# CurrentStabilizer_VER2.net
KiCad netlist of a schematic drawn in EAGLE
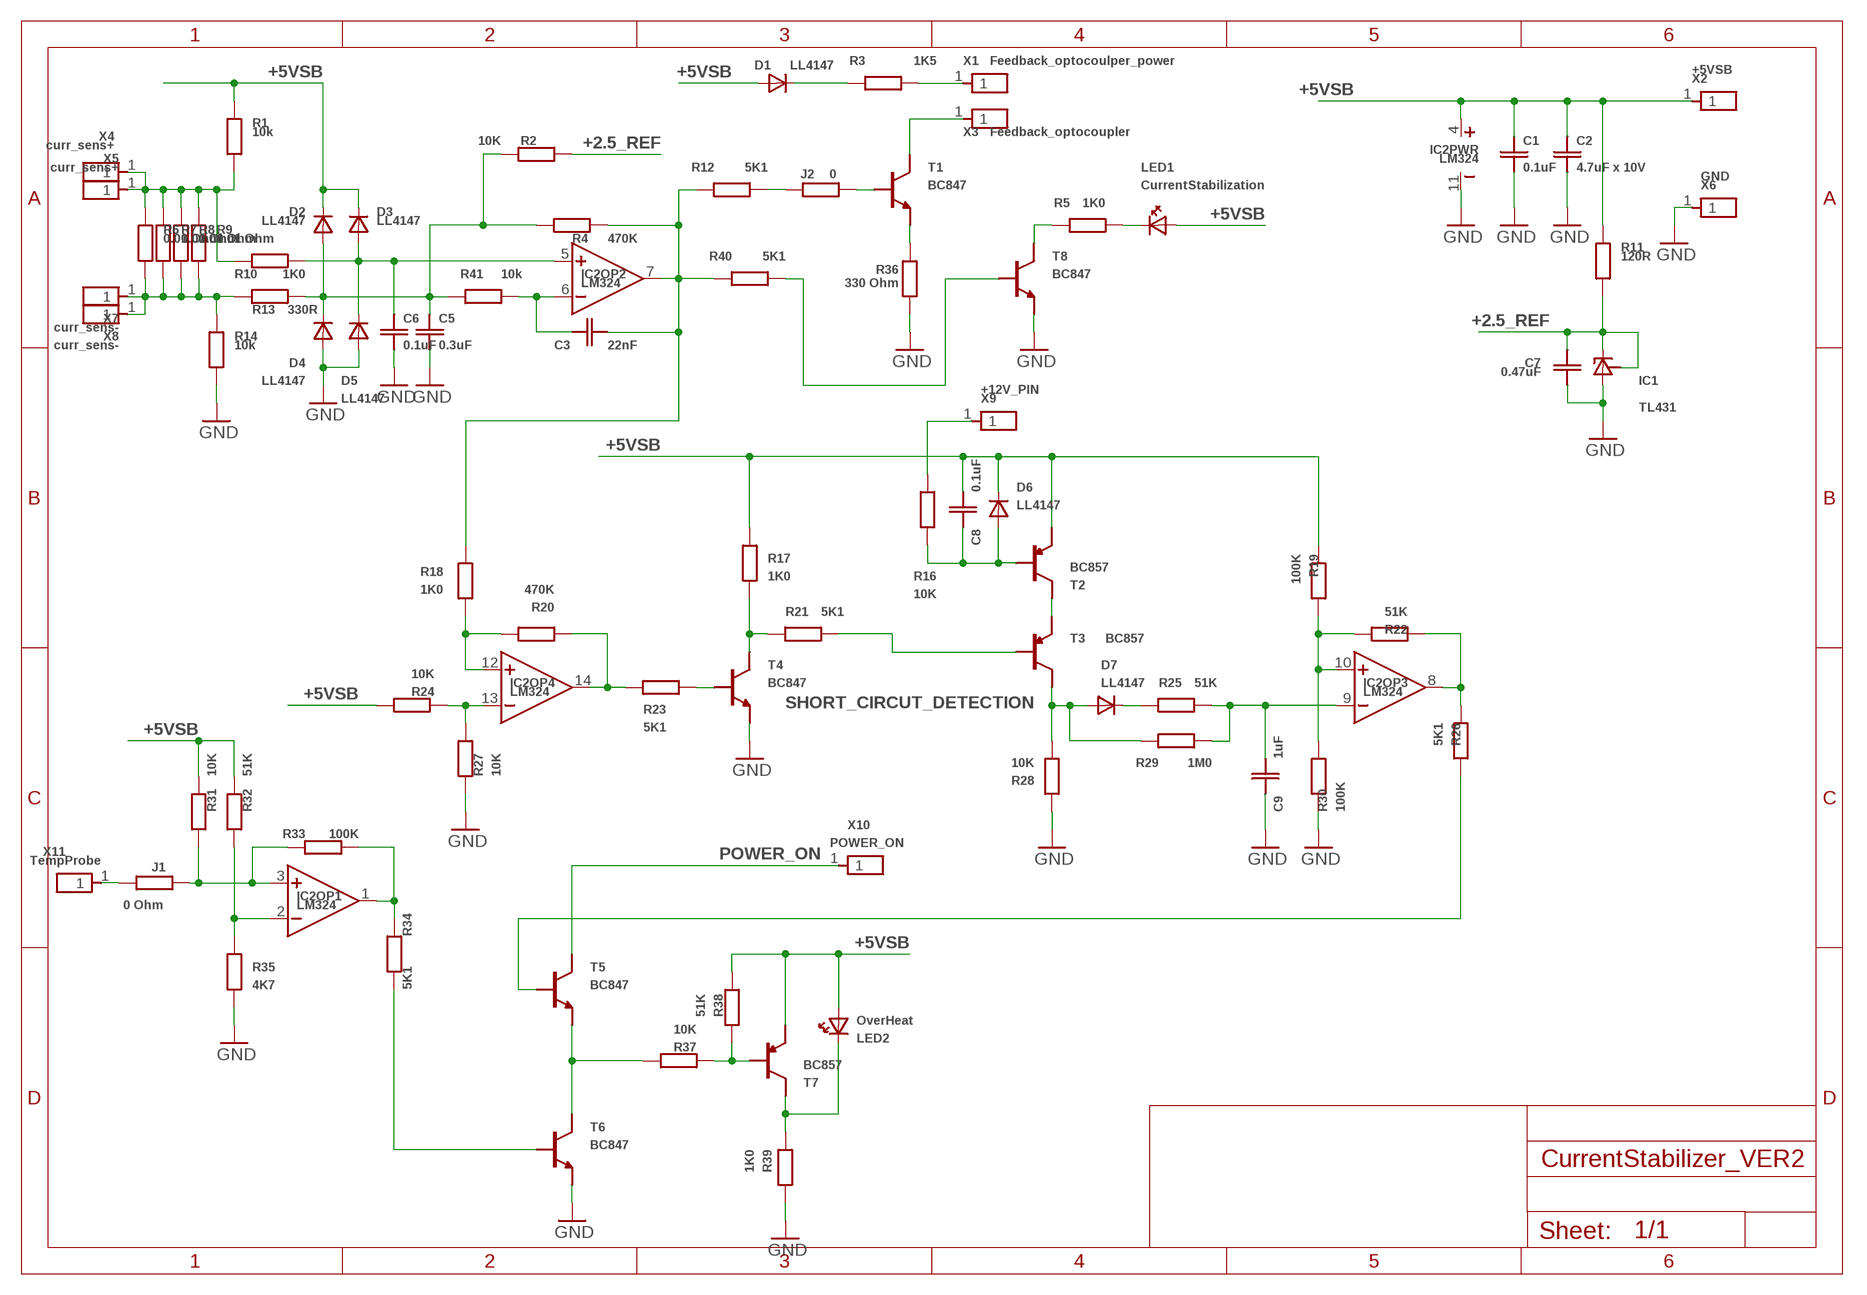
[diagram p0: schematic, sheet 1]

(export (version "E")
  (design (tool "Eeschema 10.0.6"))
  (components
    (comp (ref "C1")
      (value "0.1uF")
      (footprint "eagle-import:RSMD_0805")
      (libsource (lib "eagle-import") (part "CSMD_0805"))
    )
    (comp (ref "C2")
      (value "4.7uF x 10V")
      (footprint "eagle-import:RSMD_1206")
      (libsource (lib "eagle-import") (part "CSMD_1206"))
    )
    (comp (ref "C3")
      (value "22nF")
      (footprint "eagle-import:RSMD_0805")
      (libsource (lib "eagle-import") (part "CSMD_0805"))
    )
    (comp (ref "C5")
      (value "0.3uF")
      (footprint "eagle-import:RSMD_0805")
      (libsource (lib "eagle-import") (part "CSMD_0805"))
    )
    (comp (ref "C6")
      (value "0.1uF")
      (footprint "eagle-import:RSMD_0805")
      (libsource (lib "eagle-import") (part "CSMD_0805"))
    )
    (comp (ref "C7")
      (value "0.47uF")
      (footprint "eagle-import:RSMD_0805")
      (libsource (lib "eagle-import") (part "CSMD_0805"))
    )
    (comp (ref "C8")
      (value "0.1uF")
      (footprint "eagle-import:RSMD_0805")
      (libsource (lib "eagle-import") (part "CSMD_0805"))
    )
    (comp (ref "C9")
      (value "1uF")
      (footprint "eagle-import:RSMD_0805")
      (libsource (lib "eagle-import") (part "CSMD_0805"))
    )
    (comp (ref "D1")
      (value "LL4147")
      (footprint "eagle-import:SOD-80")
      (libsource (lib "eagle-import") (part "LL4147SOD-80"))
    )
    (comp (ref "D2")
      (value "LL4147")
      (footprint "eagle-import:SOD-80")
      (libsource (lib "eagle-import") (part "LL4147SOD-80"))
    )
    (comp (ref "D3")
      (value "LL4147")
      (footprint "eagle-import:SOD-80")
      (libsource (lib "eagle-import") (part "LL4147SOD-80"))
    )
    (comp (ref "D4")
      (value "LL4147")
      (footprint "eagle-import:SOD-80")
      (libsource (lib "eagle-import") (part "LL4147SOD-80"))
    )
    (comp (ref "D5")
      (value "LL4147")
      (footprint "eagle-import:SOD-80")
      (libsource (lib "eagle-import") (part "LL4147SOD-80"))
    )
    (comp (ref "D6")
      (value "LL4147")
      (footprint "eagle-import:SOD-80")
      (libsource (lib "eagle-import") (part "LL4147SOD-80"))
    )
    (comp (ref "D7")
      (value "LL4147")
      (footprint "eagle-import:SOD-80")
      (libsource (lib "eagle-import") (part "LL4147SOD-80"))
    )
    (comp (ref "IC1")
      (value "TL431")
      (footprint "eagle-import:SOT23")
      (libsource (lib "eagle-import") (part "TL431SOT23"))
    )
    (comp (ref "IC2")
      (value "LM324")
      (footprint "eagle-import:SOIC14")
      (libsource (lib "eagle-import") (part "LM324"))
    )
    (comp (ref "J1")
      (value "0 Ohm")
      (footprint "eagle-import:RSMD_0805")
      (libsource (lib "eagle-import") (part "RSMD_0805"))
    )
    (comp (ref "J2")
      (value "0")
      (footprint "eagle-import:RSMD_0805")
      (libsource (lib "eagle-import") (part "RSMD_0805"))
    )
    (comp (ref "LED1")
      (value "CurrentStabilization")
      (footprint "eagle-import:LED3MM")
      (libsource (lib "eagle-import") (part "LED3MM"))
    )
    (comp (ref "LED2")
      (value "OverHeat")
      (footprint "eagle-import:LED3MM")
      (libsource (lib "eagle-import") (part "LED3MM"))
    )
    (comp (ref "R1")
      (value "10k")
      (footprint "eagle-import:RSMD_0805")
      (libsource (lib "eagle-import") (part "RSMD_0805"))
    )
    (comp (ref "R2")
      (value "10K")
      (footprint "eagle-import:RSMD_0805")
      (libsource (lib "eagle-import") (part "RSMD_0805"))
    )
    (comp (ref "R3")
      (value "1K5")
      (footprint "eagle-import:RSMD_0805")
      (libsource (lib "eagle-import") (part "RSMD_0805"))
    )
    (comp (ref "R4")
      (value "470K")
      (footprint "eagle-import:RSMD_0805")
      (libsource (lib "eagle-import") (part "RSMD_0805"))
    )
    (comp (ref "R5")
      (value "1K0")
      (footprint "eagle-import:RSMD_0805")
      (libsource (lib "eagle-import") (part "RSMD_0805"))
    )
    (comp (ref "R6")
      (value "0.01 Ohm")
      (footprint "eagle-import:RSMD_2512")
      (libsource (lib "eagle-import") (part "RSMD_2512"))
    )
    (comp (ref "R7")
      (value "0.01 Ohm")
      (footprint "eagle-import:RSMD_2512")
      (libsource (lib "eagle-import") (part "RSMD_2512"))
    )
    (comp (ref "R8")
      (value "0.01 Ohm")
      (footprint "eagle-import:RSMD_2512")
      (libsource (lib "eagle-import") (part "RSMD_2512"))
    )
    (comp (ref "R9")
      (value "0.01 Ohm")
      (footprint "eagle-import:RSMD_2512")
      (libsource (lib "eagle-import") (part "RSMD_2512"))
    )
    (comp (ref "R10")
      (value "1K0")
      (footprint "eagle-import:RSMD_0805")
      (libsource (lib "eagle-import") (part "RSMD_0805"))
    )
    (comp (ref "R11")
      (value "120R")
      (footprint "eagle-import:RSMD_0805")
      (libsource (lib "eagle-import") (part "RSMD_0805"))
    )
    (comp (ref "R12")
      (value "5K1")
      (footprint "eagle-import:RSMD_0805")
      (libsource (lib "eagle-import") (part "RSMD_0805"))
    )
    (comp (ref "R13")
      (value "330R")
      (footprint "eagle-import:RSMD_0805")
      (libsource (lib "eagle-import") (part "RSMD_0805"))
    )
    (comp (ref "R14")
      (value "10k")
      (footprint "eagle-import:RSMD_0805")
      (libsource (lib "eagle-import") (part "RSMD_0805"))
    )
    (comp (ref "R16")
      (value "10K")
      (footprint "eagle-import:RSMD_0805")
      (libsource (lib "eagle-import") (part "RSMD_0805"))
    )
    (comp (ref "R17")
      (value "1K0")
      (footprint "eagle-import:RSMD_0805")
      (libsource (lib "eagle-import") (part "RSMD_0805"))
    )
    (comp (ref "R18")
      (value "1K0")
      (footprint "eagle-import:RSMD_0805")
      (libsource (lib "eagle-import") (part "RSMD_0805"))
    )
    (comp (ref "R19")
      (value "100K")
      (footprint "eagle-import:RSMD_1206_BIG_GAP")
      (libsource (lib "eagle-import") (part "RSMD_1206_BIG_GAP"))
    )
    (comp (ref "R20")
      (value "470K")
      (footprint "eagle-import:RSMD_0805")
      (libsource (lib "eagle-import") (part "RSMD_0805"))
    )
    (comp (ref "R21")
      (value "5K1")
      (footprint "eagle-import:RSMD_0805")
      (libsource (lib "eagle-import") (part "RSMD_0805"))
    )
    (comp (ref "R22")
      (value "51K")
      (footprint "eagle-import:RSMD_0805")
      (libsource (lib "eagle-import") (part "RSMD_0805"))
    )
    (comp (ref "R23")
      (value "5K1")
      (footprint "eagle-import:RSMD_1206_BIG_GAP")
      (libsource (lib "eagle-import") (part "RSMD_1206_BIG_GAP"))
    )
    (comp (ref "R24")
      (value "10K")
      (footprint "eagle-import:RSMD_0805")
      (libsource (lib "eagle-import") (part "RSMD_0805"))
    )
    (comp (ref "R25")
      (value "51K")
      (footprint "eagle-import:RSMD_0805")
      (libsource (lib "eagle-import") (part "RSMD_0805"))
    )
    (comp (ref "R26")
      (value "5K1")
      (footprint "eagle-import:RSMD_0805")
      (libsource (lib "eagle-import") (part "RSMD_0805"))
    )
    (comp (ref "R27")
      (value "10K")
      (footprint "eagle-import:RSMD_0805")
      (libsource (lib "eagle-import") (part "RSMD_0805"))
    )
    (comp (ref "R28")
      (value "10K")
      (footprint "eagle-import:RSMD_0805")
      (libsource (lib "eagle-import") (part "RSMD_0805"))
    )
    (comp (ref "R29")
      (value "1M0")
      (footprint "eagle-import:RSMD_0805")
      (libsource (lib "eagle-import") (part "RSMD_0805"))
    )
    (comp (ref "R30")
      (value "100K")
      (footprint "eagle-import:RSMD_0805")
      (libsource (lib "eagle-import") (part "RSMD_0805"))
    )
    (comp (ref "R31")
      (value "10K")
      (footprint "eagle-import:RSMD_0805")
      (libsource (lib "eagle-import") (part "RSMD_0805"))
    )
    (comp (ref "R32")
      (value "51K")
      (footprint "eagle-import:RSMD_0805")
      (libsource (lib "eagle-import") (part "RSMD_0805"))
    )
    (comp (ref "R33")
      (value "100K")
      (footprint "eagle-import:RSMD_0805")
      (libsource (lib "eagle-import") (part "RSMD_0805"))
    )
    (comp (ref "R34")
      (value "5K1")
      (footprint "eagle-import:RSMD_0805")
      (libsource (lib "eagle-import") (part "RSMD_0805"))
    )
    (comp (ref "R35")
      (value "4K7")
      (footprint "eagle-import:RSMD_0805")
      (libsource (lib "eagle-import") (part "RSMD_0805"))
    )
    (comp (ref "R36")
      (value "330 Ohm")
      (footprint "eagle-import:RSMD_0805")
      (libsource (lib "eagle-import") (part "RSMD_0805"))
    )
    (comp (ref "R37")
      (value "10K")
      (footprint "eagle-import:RSMD_1206_BIG_GAP")
      (libsource (lib "eagle-import") (part "RSMD_1206_BIG_GAP"))
    )
    (comp (ref "R38")
      (value "51K")
      (footprint "eagle-import:RSMD_0805")
      (libsource (lib "eagle-import") (part "RSMD_0805"))
    )
    (comp (ref "R39")
      (value "1K0")
      (footprint "eagle-import:RSMD_0805")
      (libsource (lib "eagle-import") (part "RSMD_0805"))
    )
    (comp (ref "R40")
      (value "5K1")
      (footprint "eagle-import:RSMD_0805")
      (libsource (lib "eagle-import") (part "RSMD_0805"))
    )
    (comp (ref "R41")
      (value "10k")
      (footprint "eagle-import:RSMD_0805")
      (libsource (lib "eagle-import") (part "RSMD_0805"))
    )
    (comp (ref "T1")
      (value "BC847")
      (footprint "eagle-import:SOT23_SMALL_PADS")
      (libsource (lib "eagle-import") (part "BC847SOT23_SMALL_PADS"))
    )
    (comp (ref "T2")
      (value "BC857")
      (footprint "eagle-import:SOT23_SMALL_PADS")
      (libsource (lib "eagle-import") (part "BC857SOT23_SMALL_PADS"))
    )
    (comp (ref "T3")
      (value "BC857")
      (footprint "eagle-import:SOT23_SMALL_PADS")
      (libsource (lib "eagle-import") (part "BC857SOT23_SMALL_PADS"))
    )
    (comp (ref "T4")
      (value "BC847")
      (footprint "eagle-import:SOT23_SMALL_PADS")
      (libsource (lib "eagle-import") (part "BC847SOT23_SMALL_PADS"))
    )
    (comp (ref "T5")
      (value "BC847")
      (footprint "eagle-import:SOT23_SMALL_PADS")
      (libsource (lib "eagle-import") (part "BC847SOT23_SMALL_PADS"))
    )
    (comp (ref "T6")
      (value "BC847")
      (footprint "eagle-import:SOT23_SMALL_PADS")
      (libsource (lib "eagle-import") (part "BC847SOT23_SMALL_PADS"))
    )
    (comp (ref "T7")
      (value "BC857")
      (footprint "eagle-import:SOT23_SMALL_PADS")
      (libsource (lib "eagle-import") (part "BC857SOT23_SMALL_PADS"))
    )
    (comp (ref "T8")
      (value "BC847")
      (footprint "eagle-import:SOT23_SMALL_PADS")
      (libsource (lib "eagle-import") (part "BC847SOT23_SMALL_PADS"))
    )
    (comp (ref "X1")
      (value "Feedback_optocoulper_power")
      (footprint "eagle-import:PIN1X1_2.54MM")
      (libsource (lib "eagle-import") (part "PIN1X12.54MM"))
    )
    (comp (ref "X2")
      (value "+5VSB")
      (footprint "eagle-import:PIN1X1_2.54MM")
      (libsource (lib "eagle-import") (part "PIN1X12.54MM"))
    )
    (comp (ref "X3")
      (value "Feedback_optocoupler")
      (footprint "eagle-import:PIN1X1_2.54MM")
      (libsource (lib "eagle-import") (part "PIN1X12.54MM"))
    )
    (comp (ref "X4")
      (value "curr_sens+")
      (footprint "eagle-import:PIN1X1_2.54MM")
      (libsource (lib "eagle-import") (part "PIN1X12.54MM"))
    )
    (comp (ref "X5")
      (value "curr_sens+")
      (footprint "eagle-import:PIN1X1_2.54MM")
      (libsource (lib "eagle-import") (part "PIN1X12.54MM"))
    )
    (comp (ref "X6")
      (value "GND")
      (footprint "eagle-import:PIN1X1_2.54MM")
      (libsource (lib "eagle-import") (part "PIN1X12.54MM"))
    )
    (comp (ref "X7")
      (value "curr_sens-")
      (footprint "eagle-import:PIN1X1_2.54MM")
      (libsource (lib "eagle-import") (part "PIN1X12.54MM"))
    )
    (comp (ref "X8")
      (value "curr_sens-")
      (footprint "eagle-import:PIN1X1_2.54MM")
      (libsource (lib "eagle-import") (part "PIN1X12.54MM"))
    )
    (comp (ref "X9")
      (value "+12V_PIN")
      (footprint "eagle-import:PIN1X1_2.54MM")
      (libsource (lib "eagle-import") (part "PIN1X12.54MM"))
    )
    (comp (ref "X10")
      (value "POWER_ON")
      (footprint "eagle-import:PIN1X1_2.54MM")
      (libsource (lib "eagle-import") (part "PIN1X12.54MM"))
    )
    (comp (ref "X11")
      (value "TempProbe")
      (footprint "eagle-import:PIN1X1_2.54MM")
      (libsource (lib "eagle-import") (part "PIN1X12.54MM"))
    )
  )
  (nets
    (net (code "1") (name "/+2.5_REF") (class "Default")
      (node (ref "C7") (pin "PAD_1") (pinfunction "PIN1_PAD_1") (pintype "bidirectional"))
      (node (ref "IC1") (pin "1") (pinfunction "CATHODE_1") (pintype "passive"))
      (node (ref "IC1") (pin "2") (pinfunction "REFERENCE_2") (pintype "passive"))
      (node (ref "R11") (pin "PAD_0") (pinfunction "PIN0_PAD_0") (pintype "passive"))
      (node (ref "R2") (pin "PAD_0") (pinfunction "PIN0_PAD_0") (pintype "passive"))
    )
    (net (code "2") (name "/+5VSB") (class "Default")
      (node (ref "C1") (pin "PAD_1") (pinfunction "PIN1_PAD_1") (pintype "bidirectional"))
      (node (ref "C2") (pin "PAD_1") (pinfunction "PIN1_PAD_1") (pintype "bidirectional"))
      (node (ref "C8") (pin "PAD_0") (pinfunction "PIN0_PAD_0") (pintype "bidirectional"))
      (node (ref "D1") (pin "ANODE") (pinfunction "ANODE_ANODE") (pintype "passive"))
      (node (ref "D2") (pin "CATHODE") (pinfunction "CATHODE_CATHODE") (pintype "passive"))
      (node (ref "D3") (pin "CATHODE") (pinfunction "CATHODE_CATHODE") (pintype "passive"))
      (node (ref "D6") (pin "CATHODE") (pinfunction "CATHODE_CATHODE") (pintype "passive"))
      (node (ref "IC2") (pin "4") (pinfunction "VCC_4") (pintype "power_in"))
      (node (ref "LED1") (pin "ANODE") (pinfunction "ANODE_ANODE") (pintype "passive"))
      (node (ref "LED2") (pin "ANODE") (pinfunction "ANODE_ANODE") (pintype "passive"))
      (node (ref "R1") (pin "PAD_1") (pinfunction "PIN1_PAD_1") (pintype "passive"))
      (node (ref "R11") (pin "PAD_1") (pinfunction "PIN1_PAD_1") (pintype "passive"))
      (node (ref "R17") (pin "PAD_0") (pinfunction "PIN0_PAD_0") (pintype "passive"))
      (node (ref "R19") (pin "PAD_0") (pinfunction "PIN0_PAD_0") (pintype "passive"))
      (node (ref "R24") (pin "PAD_1") (pinfunction "PIN1_PAD_1") (pintype "passive"))
      (node (ref "R31") (pin "PAD_1") (pinfunction "PIN1_PAD_1") (pintype "passive"))
      (node (ref "R32") (pin "PAD_1") (pinfunction "PIN1_PAD_1") (pintype "passive"))
      (node (ref "R38") (pin "PAD_0") (pinfunction "PIN0_PAD_0") (pintype "passive"))
      (node (ref "T2") (pin "2") (pinfunction "E_2") (pintype "bidirectional"))
      (node (ref "T7") (pin "2") (pinfunction "E_2") (pintype "bidirectional"))
      (node (ref "X2") (pin "1") (pinfunction "1_1") (pintype "bidirectional"))
    )
    (net (code "3") (name "/POWER_ON") (class "Default")
      (node (ref "T5") (pin "3") (pinfunction "C_3") (pintype "bidirectional"))
      (node (ref "X10") (pin "1") (pinfunction "1_1") (pintype "bidirectional"))
    )
    (net (code "4") (name "/SHORT_CIRCUT_DETECTION") (class "Default")
      (node (ref "D7") (pin "ANODE") (pinfunction "ANODE_ANODE") (pintype "passive"))
      (node (ref "R28") (pin "PAD_0") (pinfunction "PIN0_PAD_0") (pintype "passive"))
      (node (ref "R29") (pin "PAD_1") (pinfunction "PIN1_PAD_1") (pintype "passive"))
      (node (ref "T3") (pin "3") (pinfunction "C_3") (pintype "bidirectional"))
    )
    (net (code "5") (name "GND") (class "Default")
      (node (ref "C1") (pin "PAD_0") (pinfunction "PIN0_PAD_0") (pintype "bidirectional"))
      (node (ref "C2") (pin "PAD_0") (pinfunction "PIN0_PAD_0") (pintype "bidirectional"))
      (node (ref "C5") (pin "PAD_0") (pinfunction "PIN0_PAD_0") (pintype "bidirectional"))
      (node (ref "C6") (pin "PAD_0") (pinfunction "PIN0_PAD_0") (pintype "bidirectional"))
      (node (ref "C7") (pin "PAD_0") (pinfunction "PIN0_PAD_0") (pintype "bidirectional"))
      (node (ref "C9") (pin "PAD_1") (pinfunction "PIN1_PAD_1") (pintype "bidirectional"))
      (node (ref "D4") (pin "ANODE") (pinfunction "ANODE_ANODE") (pintype "passive"))
      (node (ref "D5") (pin "ANODE") (pinfunction "ANODE_ANODE") (pintype "passive"))
      (node (ref "IC1") (pin "3") (pinfunction "ANODE_3") (pintype "passive"))
      (node (ref "IC2") (pin "11") (pinfunction "GND_11") (pintype "power_in"))
      (node (ref "R14") (pin "PAD_0") (pinfunction "PIN0_PAD_0") (pintype "passive"))
      (node (ref "R27") (pin "PAD_0") (pinfunction "PIN0_PAD_0") (pintype "passive"))
      (node (ref "R28") (pin "PAD_1") (pinfunction "PIN1_PAD_1") (pintype "passive"))
      (node (ref "R30") (pin "PAD_0") (pinfunction "PIN0_PAD_0") (pintype "passive"))
      (node (ref "R35") (pin "PAD_0") (pinfunction "PIN0_PAD_0") (pintype "passive"))
      (node (ref "R36") (pin "PAD_0") (pinfunction "PIN0_PAD_0") (pintype "passive"))
      (node (ref "R39") (pin "PAD_1") (pinfunction "PIN1_PAD_1") (pintype "passive"))
      (node (ref "T4") (pin "2") (pinfunction "E_2") (pintype "bidirectional"))
      (node (ref "T6") (pin "2") (pinfunction "E_2") (pintype "bidirectional"))
      (node (ref "T8") (pin "2") (pinfunction "E_2") (pintype "bidirectional"))
      (node (ref "X6") (pin "1") (pinfunction "1_1") (pintype "bidirectional"))
    )
    (net (code "6") (name "Net-(C3-PIN0)") (class "Default")
      (node (ref "C3") (pin "PAD_0") (pinfunction "PIN0_PAD_0") (pintype "bidirectional"))
      (node (ref "IC2") (pin "7") (pinfunction "OUT_7") (pintype "output"))
      (node (ref "R12") (pin "PAD_1") (pinfunction "PIN1_PAD_1") (pintype "passive"))
      (node (ref "R18") (pin "PAD_1") (pinfunction "PIN1_PAD_1") (pintype "passive"))
      (node (ref "R4") (pin "PAD_1") (pinfunction "PIN1_PAD_1") (pintype "passive"))
      (node (ref "R40") (pin "PAD_1") (pinfunction "PIN1_PAD_1") (pintype "passive"))
    )
    (net (code "7") (name "Net-(C3-PIN1)") (class "Default")
      (node (ref "C3") (pin "PAD_1") (pinfunction "PIN1_PAD_1") (pintype "bidirectional"))
      (node (ref "IC2") (pin "6") (pinfunction "IN-_6") (pintype "input"))
      (node (ref "R41") (pin "PAD_0") (pinfunction "PIN0_PAD_0") (pintype "passive"))
    )
    (net (code "8") (name "Net-(C5-PIN1)") (class "Default")
      (node (ref "C5") (pin "PAD_1") (pinfunction "PIN1_PAD_1") (pintype "bidirectional"))
      (node (ref "D2") (pin "ANODE") (pinfunction "ANODE_ANODE") (pintype "passive"))
      (node (ref "D4") (pin "CATHODE") (pinfunction "CATHODE_CATHODE") (pintype "passive"))
      (node (ref "R13") (pin "PAD_1") (pinfunction "PIN1_PAD_1") (pintype "passive"))
      (node (ref "R2") (pin "PAD_1") (pinfunction "PIN1_PAD_1") (pintype "passive"))
      (node (ref "R4") (pin "PAD_0") (pinfunction "PIN0_PAD_0") (pintype "passive"))
      (node (ref "R41") (pin "PAD_1") (pinfunction "PIN1_PAD_1") (pintype "passive"))
    )
    (net (code "9") (name "Net-(C6-PIN1)") (class "Default")
      (node (ref "C6") (pin "PAD_1") (pinfunction "PIN1_PAD_1") (pintype "bidirectional"))
      (node (ref "D3") (pin "ANODE") (pinfunction "ANODE_ANODE") (pintype "passive"))
      (node (ref "D5") (pin "CATHODE") (pinfunction "CATHODE_CATHODE") (pintype "passive"))
      (node (ref "IC2") (pin "5") (pinfunction "IN+_5") (pintype "input"))
      (node (ref "R10") (pin "PAD_1") (pinfunction "PIN1_PAD_1") (pintype "passive"))
    )
    (net (code "10") (name "Net-(C8-PIN1)") (class "Default")
      (node (ref "C8") (pin "PAD_1") (pinfunction "PIN1_PAD_1") (pintype "bidirectional"))
      (node (ref "D6") (pin "ANODE") (pinfunction "ANODE_ANODE") (pintype "passive"))
      (node (ref "R16") (pin "PAD_1") (pinfunction "PIN1_PAD_1") (pintype "passive"))
      (node (ref "T2") (pin "1") (pinfunction "B_1") (pintype "bidirectional"))
    )
    (net (code "11") (name "Net-(C9-PIN0)") (class "Default")
      (node (ref "C9") (pin "PAD_0") (pinfunction "PIN0_PAD_0") (pintype "bidirectional"))
      (node (ref "IC2") (pin "9") (pinfunction "IN-_9") (pintype "input"))
      (node (ref "R25") (pin "PAD_1") (pinfunction "PIN1_PAD_1") (pintype "passive"))
      (node (ref "R29") (pin "PAD_0") (pinfunction "PIN0_PAD_0") (pintype "passive"))
    )
    (net (code "12") (name "Net-(IC2A-IN+)") (class "Default")
      (node (ref "IC2") (pin "3") (pinfunction "IN+_3") (pintype "input"))
      (node (ref "J1") (pin "PAD_0") (pinfunction "PIN0_PAD_0") (pintype "passive"))
      (node (ref "R31") (pin "PAD_0") (pinfunction "PIN0_PAD_0") (pintype "passive"))
      (node (ref "R33") (pin "PAD_1") (pinfunction "PIN1_PAD_1") (pintype "passive"))
    )
    (net (code "13") (name "Net-(IC2A-IN-)") (class "Default")
      (node (ref "IC2") (pin "2") (pinfunction "IN-_2") (pintype "input"))
      (node (ref "R32") (pin "PAD_0") (pinfunction "PIN0_PAD_0") (pintype "passive"))
      (node (ref "R35") (pin "PAD_1") (pinfunction "PIN1_PAD_1") (pintype "passive"))
    )
    (net (code "14") (name "Net-(IC2A-OUT)") (class "Default")
      (node (ref "IC2") (pin "1") (pinfunction "OUT_1") (pintype "output"))
      (node (ref "R33") (pin "PAD_0") (pinfunction "PIN0_PAD_0") (pintype "passive"))
      (node (ref "R34") (pin "PAD_1") (pinfunction "PIN1_PAD_1") (pintype "passive"))
    )
    (net (code "15") (name "Net-(IC2C-IN+)") (class "Default")
      (node (ref "IC2") (pin "10") (pinfunction "IN+_10") (pintype "input"))
      (node (ref "R19") (pin "PAD_1") (pinfunction "PIN1_PAD_1") (pintype "passive"))
      (node (ref "R22") (pin "PAD_1") (pinfunction "PIN1_PAD_1") (pintype "passive"))
      (node (ref "R30") (pin "PAD_1") (pinfunction "PIN1_PAD_1") (pintype "passive"))
    )
    (net (code "16") (name "Net-(IC2C-OUT)") (class "Default")
      (node (ref "IC2") (pin "8") (pinfunction "OUT_8") (pintype "output"))
      (node (ref "R22") (pin "PAD_0") (pinfunction "PIN0_PAD_0") (pintype "passive"))
      (node (ref "R26") (pin "PAD_0") (pinfunction "PIN0_PAD_0") (pintype "passive"))
    )
    (net (code "17") (name "Net-(IC2D-IN+)") (class "Default")
      (node (ref "IC2") (pin "12") (pinfunction "IN+_12") (pintype "input"))
      (node (ref "R18") (pin "PAD_0") (pinfunction "PIN0_PAD_0") (pintype "passive"))
      (node (ref "R20") (pin "PAD_0") (pinfunction "PIN0_PAD_0") (pintype "passive"))
    )
    (net (code "18") (name "Net-(IC2D-IN-)") (class "Default")
      (node (ref "IC2") (pin "13") (pinfunction "IN-_13") (pintype "input"))
      (node (ref "R24") (pin "PAD_0") (pinfunction "PIN0_PAD_0") (pintype "passive"))
      (node (ref "R27") (pin "PAD_1") (pinfunction "PIN1_PAD_1") (pintype "passive"))
    )
    (net (code "19") (name "Net-(IC2D-OUT)") (class "Default")
      (node (ref "IC2") (pin "14") (pinfunction "OUT_14") (pintype "output"))
      (node (ref "R20") (pin "PAD_1") (pinfunction "PIN1_PAD_1") (pintype "passive"))
      (node (ref "R23") (pin "PAD_1") (pinfunction "PIN1_PAD_1") (pintype "passive"))
    )
    (net (code "20") (name "Net-(J1-PIN1)") (class "Default")
      (node (ref "J1") (pin "PAD_1") (pinfunction "PIN1_PAD_1") (pintype "passive"))
      (node (ref "X11") (pin "1") (pinfunction "1_1") (pintype "bidirectional"))
    )
    (net (code "21") (name "Net-(J2-PIN0)") (class "Default")
      (node (ref "J2") (pin "PAD_0") (pinfunction "PIN0_PAD_0") (pintype "passive"))
      (node (ref "T1") (pin "1") (pinfunction "B_1") (pintype "bidirectional"))
    )
    (net (code "22") (name "Net-(J2-PIN1)") (class "Default")
      (node (ref "J2") (pin "PAD_1") (pinfunction "PIN1_PAD_1") (pintype "passive"))
      (node (ref "R12") (pin "PAD_0") (pinfunction "PIN0_PAD_0") (pintype "passive"))
    )
    (net (code "23") (name "Net-(R1-PIN0)") (class "Default")
      (node (ref "R1") (pin "PAD_0") (pinfunction "PIN0_PAD_0") (pintype "passive"))
      (node (ref "R10") (pin "PAD_0") (pinfunction "PIN0_PAD_0") (pintype "passive"))
      (node (ref "R6") (pin "PAD1") (pinfunction "PIN1_PAD1") (pintype "passive"))
      (node (ref "R7") (pin "PAD1") (pinfunction "PIN1_PAD1") (pintype "passive"))
      (node (ref "R8") (pin "PAD1") (pinfunction "PIN1_PAD1") (pintype "passive"))
      (node (ref "R9") (pin "PAD1") (pinfunction "PIN1_PAD1") (pintype "passive"))
      (node (ref "X4") (pin "1") (pinfunction "1_1") (pintype "bidirectional"))
      (node (ref "X5") (pin "1") (pinfunction "1_1") (pintype "bidirectional"))
    )
    (net (code "24") (name "Net-(R3-PIN0)") (class "Default")
      (node (ref "R3") (pin "PAD_0") (pinfunction "PIN0_PAD_0") (pintype "passive"))
      (node (ref "X1") (pin "1") (pinfunction "1_1") (pintype "bidirectional"))
    )
    (net (code "25") (name "Net-(R3-PIN1)") (class "Default")
      (node (ref "D1") (pin "CATHODE") (pinfunction "CATHODE_CATHODE") (pintype "passive"))
      (node (ref "R3") (pin "PAD_1") (pinfunction "PIN1_PAD_1") (pintype "passive"))
    )
    (net (code "26") (name "Net-(R5-PIN0)") (class "Default")
      (node (ref "LED1") (pin "CATHODE") (pinfunction "CATHODE_CATHODE") (pintype "passive"))
      (node (ref "R5") (pin "PAD_0") (pinfunction "PIN0_PAD_0") (pintype "passive"))
    )
    (net (code "27") (name "Net-(R5-PIN1)") (class "Default")
      (node (ref "R5") (pin "PAD_1") (pinfunction "PIN1_PAD_1") (pintype "passive"))
      (node (ref "T8") (pin "3") (pinfunction "C_3") (pintype "bidirectional"))
    )
    (net (code "28") (name "Net-(R13-PIN0)") (class "Default")
      (node (ref "R13") (pin "PAD_0") (pinfunction "PIN0_PAD_0") (pintype "passive"))
      (node (ref "R14") (pin "PAD_1") (pinfunction "PIN1_PAD_1") (pintype "passive"))
      (node (ref "R6") (pin "PAD0") (pinfunction "PIN0_PAD0") (pintype "passive"))
      (node (ref "R7") (pin "PAD0") (pinfunction "PIN0_PAD0") (pintype "passive"))
      (node (ref "R8") (pin "PAD0") (pinfunction "PIN0_PAD0") (pintype "passive"))
      (node (ref "R9") (pin "PAD0") (pinfunction "PIN0_PAD0") (pintype "passive"))
      (node (ref "X7") (pin "1") (pinfunction "1_1") (pintype "bidirectional"))
      (node (ref "X8") (pin "1") (pinfunction "1_1") (pintype "bidirectional"))
    )
    (net (code "29") (name "Net-(R16-PIN0)") (class "Default")
      (node (ref "R16") (pin "PAD_0") (pinfunction "PIN0_PAD_0") (pintype "passive"))
      (node (ref "X9") (pin "1") (pinfunction "1_1") (pintype "bidirectional"))
    )
    (net (code "30") (name "Net-(R17-PIN1)") (class "Default")
      (node (ref "R17") (pin "PAD_1") (pinfunction "PIN1_PAD_1") (pintype "passive"))
      (node (ref "R21") (pin "PAD_0") (pinfunction "PIN0_PAD_0") (pintype "passive"))
      (node (ref "T4") (pin "3") (pinfunction "C_3") (pintype "bidirectional"))
    )
    (net (code "31") (name "Net-(R21-PIN1)") (class "Default")
      (node (ref "R21") (pin "PAD_1") (pinfunction "PIN1_PAD_1") (pintype "passive"))
      (node (ref "T3") (pin "1") (pinfunction "B_1") (pintype "bidirectional"))
    )
    (net (code "32") (name "Net-(R23-PIN0)") (class "Default")
      (node (ref "R23") (pin "PAD_0") (pinfunction "PIN0_PAD_0") (pintype "passive"))
      (node (ref "T4") (pin "1") (pinfunction "B_1") (pintype "bidirectional"))
    )
    (net (code "33") (name "Net-(R25-PIN0)") (class "Default")
      (node (ref "D7") (pin "CATHODE") (pinfunction "CATHODE_CATHODE") (pintype "passive"))
      (node (ref "R25") (pin "PAD_0") (pinfunction "PIN0_PAD_0") (pintype "passive"))
    )
    (net (code "34") (name "Net-(R26-PIN1)") (class "Default")
      (node (ref "R26") (pin "PAD_1") (pinfunction "PIN1_PAD_1") (pintype "passive"))
      (node (ref "T5") (pin "1") (pinfunction "B_1") (pintype "bidirectional"))
    )
    (net (code "35") (name "Net-(R34-PIN0)") (class "Default")
      (node (ref "R34") (pin "PAD_0") (pinfunction "PIN0_PAD_0") (pintype "passive"))
      (node (ref "T6") (pin "1") (pinfunction "B_1") (pintype "bidirectional"))
    )
    (net (code "36") (name "Net-(R36-PIN1)") (class "Default")
      (node (ref "R36") (pin "PAD_1") (pinfunction "PIN1_PAD_1") (pintype "passive"))
      (node (ref "T1") (pin "2") (pinfunction "E_2") (pintype "bidirectional"))
    )
    (net (code "37") (name "Net-(R37-PIN0)") (class "Default")
      (node (ref "R37") (pin "PAD_0") (pinfunction "PIN0_PAD_0") (pintype "passive"))
      (node (ref "R38") (pin "PAD_1") (pinfunction "PIN1_PAD_1") (pintype "passive"))
      (node (ref "T7") (pin "1") (pinfunction "B_1") (pintype "bidirectional"))
    )
    (net (code "38") (name "Net-(R37-PIN1)") (class "Default")
      (node (ref "R37") (pin "PAD_1") (pinfunction "PIN1_PAD_1") (pintype "passive"))
      (node (ref "T5") (pin "2") (pinfunction "E_2") (pintype "bidirectional"))
      (node (ref "T6") (pin "3") (pinfunction "C_3") (pintype "bidirectional"))
    )
    (net (code "39") (name "Net-(R39-PIN0)") (class "Default")
      (node (ref "LED2") (pin "CATHODE") (pinfunction "CATHODE_CATHODE") (pintype "passive"))
      (node (ref "R39") (pin "PAD_0") (pinfunction "PIN0_PAD_0") (pintype "passive"))
      (node (ref "T7") (pin "3") (pinfunction "C_3") (pintype "bidirectional"))
    )
    (net (code "40") (name "Net-(R40-PIN0)") (class "Default")
      (node (ref "R40") (pin "PAD_0") (pinfunction "PIN0_PAD_0") (pintype "passive"))
      (node (ref "T8") (pin "1") (pinfunction "B_1") (pintype "bidirectional"))
    )
    (net (code "41") (name "Net-(T1-C)") (class "Default")
      (node (ref "T1") (pin "3") (pinfunction "C_3") (pintype "bidirectional"))
      (node (ref "X3") (pin "1") (pinfunction "1_1") (pintype "bidirectional"))
    )
    (net (code "42") (name "Net-(T2-C)") (class "Default")
      (node (ref "T2") (pin "3") (pinfunction "C_3") (pintype "bidirectional"))
      (node (ref "T3") (pin "2") (pinfunction "E_2") (pintype "bidirectional"))
    )
  )
)
